# TSOC-ESP8266-EM.net
KiCad netlist of a schematic drawn in EAGLE
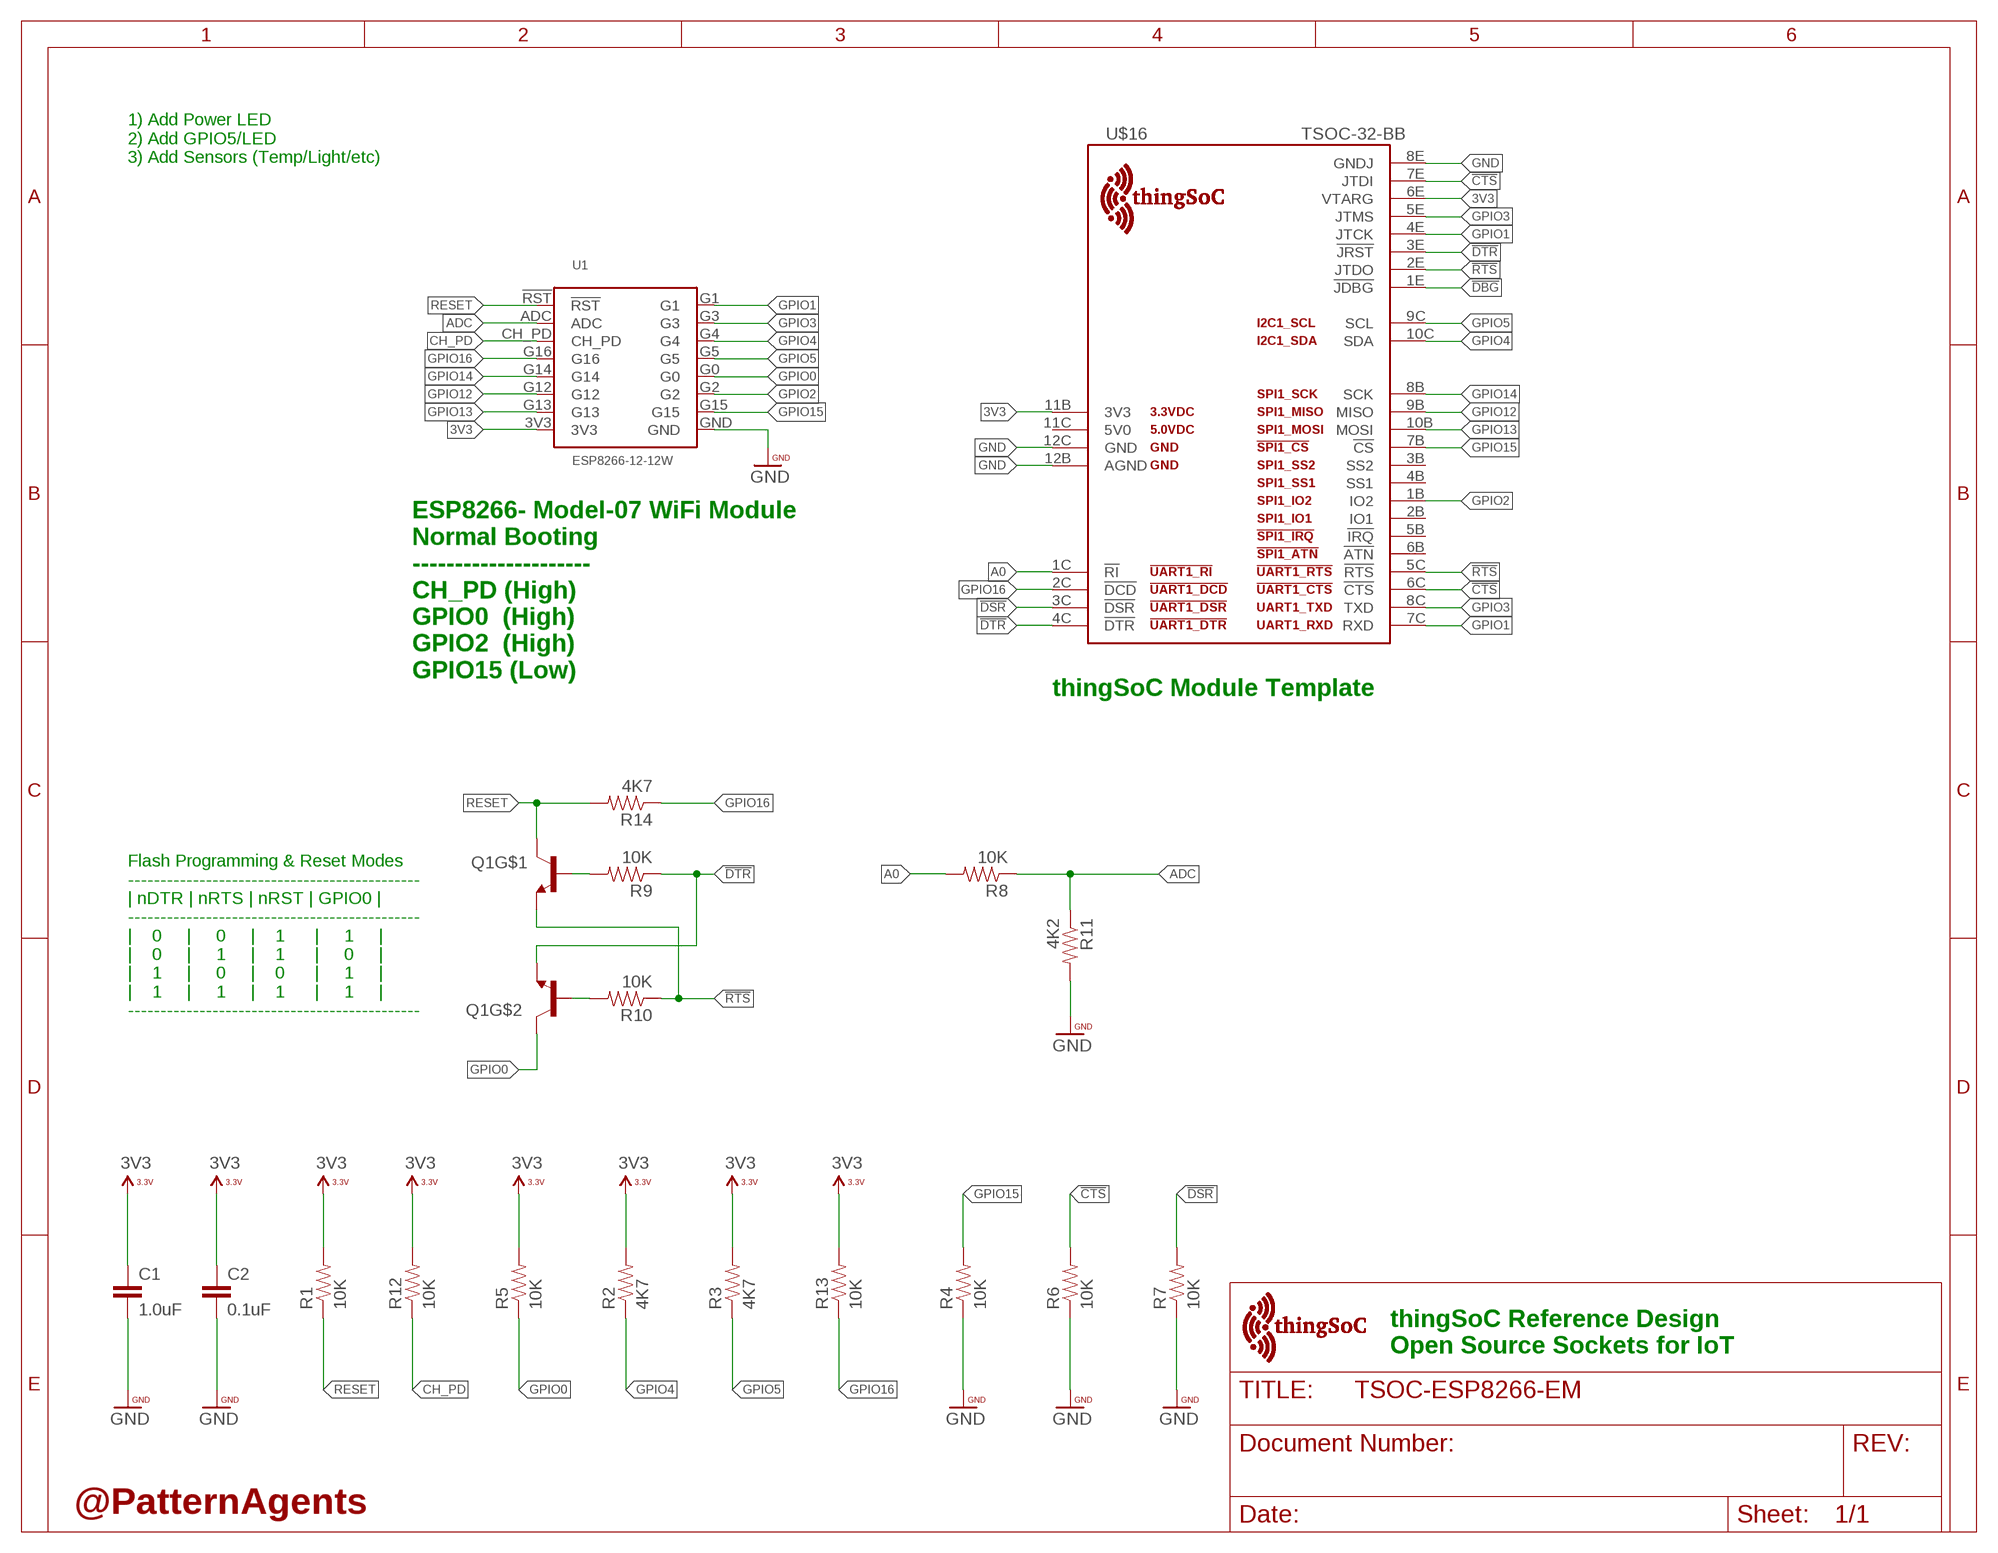
[diagram p0: schematic, sheet 1]

(export (version "E")
  (design (tool "Eeschema 10.0.6"))
  (components
    (comp (ref "C1")
      (value "1.0uF")
      (footprint "eagle-import:0402-CAP")
      (libsource (lib "eagle-import") (part "CAP0402-CAP"))
    )
    (comp (ref "C2")
      (value "0.1uF")
      (footprint "eagle-import:0402-CAP")
      (libsource (lib "eagle-import") (part "CAP0402-CAP"))
    )
    (comp (ref "Q1")
      (value "MMBT2222A")
      (footprint "eagle-import:SOT363")
      (libsource (lib "eagle-import") (part "MMDT3904"))
    )
    (comp (ref "R1")
      (value "10K")
      (footprint "eagle-import:0402-RES")
      (libsource (lib "eagle-import") (part "RESISTOR0402"))
    )
    (comp (ref "R2")
      (value "4K7")
      (footprint "eagle-import:0402-RES")
      (libsource (lib "eagle-import") (part "RESISTOR0402"))
    )
    (comp (ref "R3")
      (value "4K7")
      (footprint "eagle-import:0402-RES")
      (libsource (lib "eagle-import") (part "RESISTOR0402"))
    )
    (comp (ref "R4")
      (value "10K")
      (footprint "eagle-import:0402-RES")
      (libsource (lib "eagle-import") (part "RESISTOR0402"))
    )
    (comp (ref "R5")
      (value "10K")
      (footprint "eagle-import:0402-RES")
      (libsource (lib "eagle-import") (part "RESISTOR0402"))
    )
    (comp (ref "R6")
      (value "10K")
      (footprint "eagle-import:0402-RES")
      (libsource (lib "eagle-import") (part "RESISTOR0402"))
    )
    (comp (ref "R7")
      (value "10K")
      (footprint "eagle-import:0402-RES")
      (libsource (lib "eagle-import") (part "RESISTOR0402"))
    )
    (comp (ref "R8")
      (value "10K")
      (footprint "eagle-import:0402-RES")
      (libsource (lib "eagle-import") (part "RESISTOR0402"))
    )
    (comp (ref "R9")
      (value "10K")
      (footprint "eagle-import:0402-RES")
      (libsource (lib "eagle-import") (part "RESISTOR0402"))
    )
    (comp (ref "R10")
      (value "10K")
      (footprint "eagle-import:0402-RES")
      (libsource (lib "eagle-import") (part "RESISTOR0402"))
    )
    (comp (ref "R11")
      (value "4K2")
      (footprint "eagle-import:0402-RES")
      (libsource (lib "eagle-import") (part "RESISTOR0402"))
    )
    (comp (ref "R12")
      (value "10K")
      (footprint "eagle-import:0402-RES")
      (libsource (lib "eagle-import") (part "RESISTOR0402"))
    )
    (comp (ref "R13")
      (value "10K")
      (footprint "eagle-import:0402-RES")
      (libsource (lib "eagle-import") (part "RESISTOR0402"))
    )
    (comp (ref "R14")
      (value "4K7")
      (footprint "eagle-import:0402-RES")
      (libsource (lib "eagle-import") (part "RESISTOR0402"))
    )
    (comp (ref "U$16")
      (value "TSOC-32-BB")
      (footprint "eagle-import:TSOC-BB-S32")
      (libsource (lib "eagle-import") (part "TSOC-32-BB"))
    )
    (comp (ref "U$19")
      (value "TSOC-LOGO-SMALL")
      (footprint "eagle-import:TSOC-LOGO-SML")
      (libsource (lib "eagle-import") (part "TSOC-LOGO-SMALL"))
    )
    (comp (ref "U$20")
      (value "TSOC-LOGO-SMALL")
      (footprint "eagle-import:TSOC-LOGO-SML")
      (libsource (lib "eagle-import") (part "TSOC-LOGO-SMALL"))
    )
    (comp (ref "U1")
      (value "ESP8266-12-12W")
      (footprint "eagle-import:ESP8266-12W")
      (libsource (lib "eagle-import") (part "ESP8266-12-12W"))
    )
  )
  (nets
    (net (code "1") (name "/~{CTS}") (class "Default")
      (node (ref "R6") (pin "2") (pinfunction "2_2") (pintype "passive"))
      (node (ref "U$16") (pin "6C") (pinfunction "~{CTS}_6C") (pintype "bidirectional"))
      (node (ref "U$16") (pin "7E") (pinfunction "JTDI_7E") (pintype "bidirectional"))
    )
    (net (code "2") (name "/~{DBG}") (class "Default")
      (node (ref "U$16") (pin "1E") (pinfunction "~{JDBG}_1E") (pintype "bidirectional"))
    )
    (net (code "3") (name "/~{DSR}") (class "Default")
      (node (ref "R7") (pin "2") (pinfunction "2_2") (pintype "passive"))
      (node (ref "U$16") (pin "3C") (pinfunction "~{DSR}_3C") (pintype "bidirectional"))
    )
    (net (code "4") (name "/~{DTR}") (class "Default")
      (node (ref "Q1") (pin "1") (pinfunction "E_1") (pintype "passive"))
      (node (ref "R9") (pin "1") (pinfunction "1_1") (pintype "passive"))
      (node (ref "U$16") (pin "3E") (pinfunction "~{JRST}_3E") (pintype "bidirectional"))
      (node (ref "U$16") (pin "4C") (pinfunction "~{DTR}_4C") (pintype "bidirectional"))
    )
    (net (code "5") (name "/~{RTS}") (class "Default")
      (node (ref "Q1") (pin "4") (pinfunction "E_4") (pintype "passive"))
      (node (ref "R10") (pin "1") (pinfunction "1_1") (pintype "passive"))
      (node (ref "U$16") (pin "2E") (pinfunction "JTDO_2E") (pintype "bidirectional"))
      (node (ref "U$16") (pin "5C") (pinfunction "~{RTS}_5C") (pintype "bidirectional"))
    )
    (net (code "6") (name "3V3") (class "Default")
      (node (ref "C1") (pin "1") (pinfunction "1_1") (pintype "passive"))
      (node (ref "C2") (pin "1") (pinfunction "1_1") (pintype "passive"))
      (node (ref "R1") (pin "2") (pinfunction "2_2") (pintype "passive"))
      (node (ref "R12") (pin "2") (pinfunction "2_2") (pintype "passive"))
      (node (ref "R13") (pin "2") (pinfunction "2_2") (pintype "passive"))
      (node (ref "R2") (pin "2") (pinfunction "2_2") (pintype "passive"))
      (node (ref "R3") (pin "2") (pinfunction "2_2") (pintype "passive"))
      (node (ref "R5") (pin "2") (pinfunction "2_2") (pintype "passive"))
      (node (ref "U$16") (pin "11B") (pinfunction "3V3_11B") (pintype "bidirectional"))
      (node (ref "U$16") (pin "6E") (pinfunction "VTARG_6E") (pintype "bidirectional"))
      (node (ref "U1") (pin "3V3") (pinfunction "3V3_3V3") (pintype "bidirectional"))
    )
    (net (code "7") (name "A0") (class "Default")
      (node (ref "R8") (pin "2") (pinfunction "2_2") (pintype "passive"))
      (node (ref "U$16") (pin "1C") (pinfunction "~{RI}_1C") (pintype "bidirectional"))
    )
    (net (code "8") (name "ADC") (class "Default")
      (node (ref "R11") (pin "1") (pinfunction "1_1") (pintype "passive"))
      (node (ref "R8") (pin "1") (pinfunction "1_1") (pintype "passive"))
      (node (ref "U1") (pin "ADC") (pinfunction "ADC_ADC") (pintype "bidirectional"))
    )
    (net (code "9") (name "CH_PD") (class "Default")
      (node (ref "R12") (pin "1") (pinfunction "1_1") (pintype "passive"))
      (node (ref "U1") (pin "CH_PD") (pinfunction "CH_PD_CH_PD") (pintype "bidirectional"))
    )
    (net (code "10") (name "GND") (class "Default")
      (node (ref "C1") (pin "2") (pinfunction "2_2") (pintype "passive"))
      (node (ref "C2") (pin "2") (pinfunction "2_2") (pintype "passive"))
      (node (ref "R11") (pin "2") (pinfunction "2_2") (pintype "passive"))
      (node (ref "R4") (pin "1") (pinfunction "1_1") (pintype "passive"))
      (node (ref "R6") (pin "1") (pinfunction "1_1") (pintype "passive"))
      (node (ref "R7") (pin "1") (pinfunction "1_1") (pintype "passive"))
      (node (ref "U$16") (pin "12B") (pinfunction "AGND_12B") (pintype "bidirectional"))
      (node (ref "U$16") (pin "12C") (pinfunction "GND_12C") (pintype "bidirectional"))
      (node (ref "U$16") (pin "8E") (pinfunction "GNDJ_8E") (pintype "bidirectional"))
      (node (ref "U1") (pin "GND") (pinfunction "GND_GND") (pintype "bidirectional"))
    )
    (net (code "11") (name "GPIO0") (class "Default")
      (node (ref "Q1") (pin "6") (pinfunction "C_6") (pintype "passive"))
      (node (ref "R5") (pin "1") (pinfunction "1_1") (pintype "passive"))
      (node (ref "U1") (pin "G0") (pinfunction "G0_G0") (pintype "bidirectional"))
    )
    (net (code "12") (name "GPIO1") (class "Default")
      (node (ref "U$16") (pin "4E") (pinfunction "JTCK_4E") (pintype "bidirectional"))
      (node (ref "U$16") (pin "7C") (pinfunction "RXD_7C") (pintype "bidirectional"))
      (node (ref "U1") (pin "G1") (pinfunction "G1_G1") (pintype "bidirectional"))
    )
    (net (code "13") (name "GPIO2") (class "Default")
      (node (ref "U$16") (pin "1B") (pinfunction "IO2_1B") (pintype "bidirectional"))
      (node (ref "U1") (pin "G2") (pinfunction "G2_G2") (pintype "bidirectional"))
    )
    (net (code "14") (name "GPIO3") (class "Default")
      (node (ref "U$16") (pin "5E") (pinfunction "JTMS_5E") (pintype "bidirectional"))
      (node (ref "U$16") (pin "8C") (pinfunction "TXD_8C") (pintype "bidirectional"))
      (node (ref "U1") (pin "G3") (pinfunction "G3_G3") (pintype "bidirectional"))
    )
    (net (code "15") (name "GPIO4") (class "Default")
      (node (ref "R2") (pin "1") (pinfunction "1_1") (pintype "passive"))
      (node (ref "U$16") (pin "10C") (pinfunction "SDA_10C") (pintype "bidirectional"))
      (node (ref "U1") (pin "G4") (pinfunction "G4_G4") (pintype "bidirectional"))
    )
    (net (code "16") (name "GPIO5") (class "Default")
      (node (ref "R3") (pin "1") (pinfunction "1_1") (pintype "passive"))
      (node (ref "U$16") (pin "9C") (pinfunction "SCL_9C") (pintype "bidirectional"))
      (node (ref "U1") (pin "G5") (pinfunction "G5_G5") (pintype "bidirectional"))
    )
    (net (code "17") (name "GPIO12") (class "Default")
      (node (ref "U$16") (pin "9B") (pinfunction "MISO_9B") (pintype "bidirectional"))
      (node (ref "U1") (pin "G12") (pinfunction "G12_G12") (pintype "bidirectional"))
    )
    (net (code "18") (name "GPIO13") (class "Default")
      (node (ref "U$16") (pin "10B") (pinfunction "MOSI_10B") (pintype "bidirectional"))
      (node (ref "U1") (pin "G13") (pinfunction "G13_G13") (pintype "bidirectional"))
    )
    (net (code "19") (name "GPIO14") (class "Default")
      (node (ref "U$16") (pin "8B") (pinfunction "SCK_8B") (pintype "bidirectional"))
      (node (ref "U1") (pin "G14") (pinfunction "G14_G14") (pintype "bidirectional"))
    )
    (net (code "20") (name "GPIO15") (class "Default")
      (node (ref "R4") (pin "2") (pinfunction "2_2") (pintype "passive"))
      (node (ref "U$16") (pin "7B") (pinfunction "~{CS}_7B") (pintype "bidirectional"))
      (node (ref "U1") (pin "G15") (pinfunction "G15_G15") (pintype "bidirectional"))
    )
    (net (code "21") (name "GPIO16") (class "Default")
      (node (ref "R13") (pin "1") (pinfunction "1_1") (pintype "passive"))
      (node (ref "R14") (pin "1") (pinfunction "1_1") (pintype "passive"))
      (node (ref "U$16") (pin "2C") (pinfunction "~{DCD}_2C") (pintype "bidirectional"))
      (node (ref "U1") (pin "G16") (pinfunction "G16_G16") (pintype "bidirectional"))
    )
    (net (code "22") (name "Net-(Q1A-B)") (class "Default")
      (node (ref "Q1") (pin "5") (pinfunction "B_5") (pintype "passive"))
      (node (ref "R9") (pin "2") (pinfunction "2_2") (pintype "passive"))
    )
    (net (code "23") (name "Net-(Q1B-B)") (class "Default")
      (node (ref "Q1") (pin "2") (pinfunction "B_2") (pintype "passive"))
      (node (ref "R10") (pin "2") (pinfunction "2_2") (pintype "passive"))
    )
    (net (code "24") (name "RESET") (class "Default")
      (node (ref "Q1") (pin "3") (pinfunction "C_3") (pintype "passive"))
      (node (ref "R1") (pin "1") (pinfunction "1_1") (pintype "passive"))
      (node (ref "R14") (pin "2") (pinfunction "2_2") (pintype "passive"))
      (node (ref "U1") (pin "!RST") (pinfunction "~{RST}_!RST") (pintype "bidirectional"))
    )
    (net (code "25") (name "unconnected-(U$16-5V0-Pad11C)") (class "Default")
      (node (ref "U$16") (pin "11C") (pinfunction "5V0_11C") (pintype "bidirectional"))
    )
    (net (code "26") (name "unconnected-(U$16-IO1-Pad2B)") (class "Default")
      (node (ref "U$16") (pin "2B") (pinfunction "IO1_2B") (pintype "bidirectional"))
    )
    (net (code "27") (name "unconnected-(U$16-SS1-Pad4B)") (class "Default")
      (node (ref "U$16") (pin "4B") (pinfunction "SS1_4B") (pintype "bidirectional"))
    )
    (net (code "28") (name "unconnected-(U$16-SS2-Pad3B)") (class "Default")
      (node (ref "U$16") (pin "3B") (pinfunction "SS2_3B") (pintype "bidirectional"))
    )
    (net (code "29") (name "unconnected-(U$16-~{ATN}-Pad6B)") (class "Default")
      (node (ref "U$16") (pin "6B") (pinfunction "~{ATN}_6B") (pintype "bidirectional"))
    )
    (net (code "30") (name "unconnected-(U$16-~{IRQ}-Pad5B)") (class "Default")
      (node (ref "U$16") (pin "5B") (pinfunction "~{IRQ}_5B") (pintype "bidirectional"))
    )
  )
)
